# BPC_PWR_Temp_Sensor.net
KiCad netlist of a schematic drawn in Altium Designer
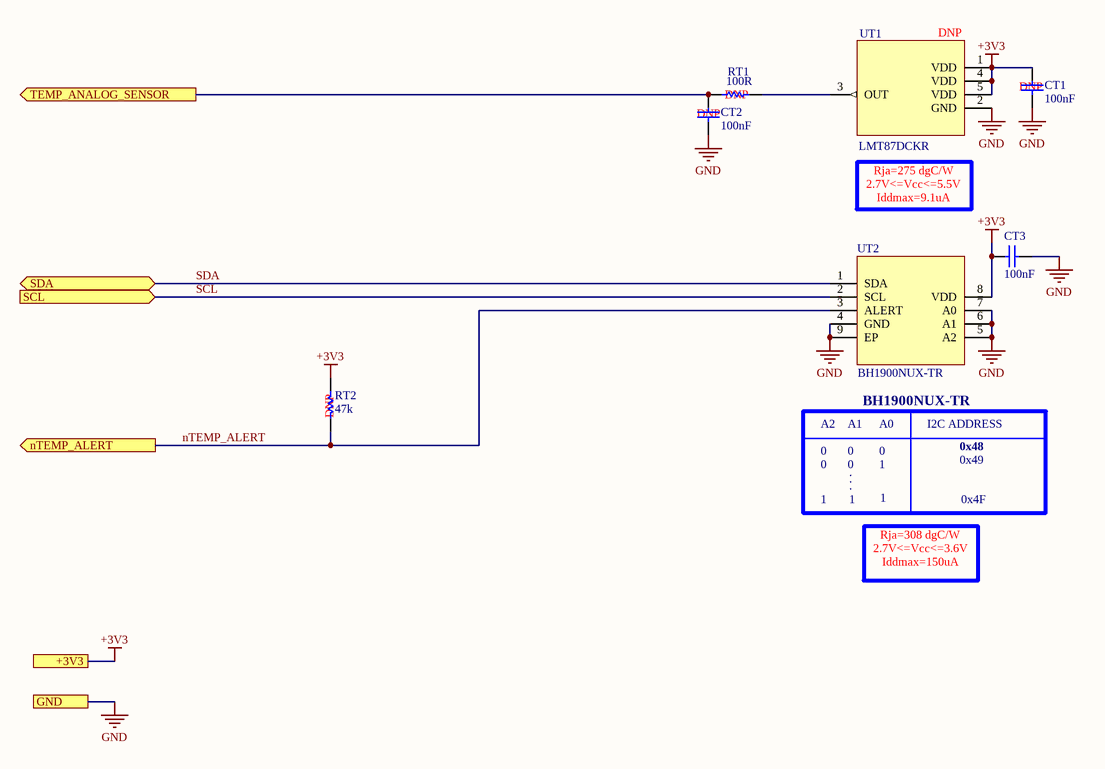
[diagram p0: BPC_PWR_Temp_Sensor.SchDoc]

(export (version "E")
  (design (tool "Eeschema 10.0.6"))
  (components
    (comp (ref "CT1")
      (value "Ceramic Capacitor")
      (footprint "C0603L 0.8 MM MS")
      (description "Ceramic Capacitor 100nF 50V X7R 0603")
      (fields
        (field (name "DISTRIBUTOR PART NUMBER") "187-CL10B104KB8WPNC")
        (field (name "MANUFACTURER") "Samsung Electro-Mechanics")
        (field (name "POPULATED") "DNP")
        (field (name "CAPACITANCE") "100nF")
      )
      (libsource (lib "MS IMP Library") (part "Cap Cer 100nF 50V X7R 0603 Pt02"))
    )
    (comp (ref "CT2")
      (value "Ceramic Capacitor")
      (footprint "C0603L 0.8 MM MS")
      (description "Ceramic Capacitor 100nF 50V X7R 0603")
      (fields
        (field (name "DISTRIBUTOR PART NUMBER") "187-CL10B104KB8WPNC")
        (field (name "MANUFACTURER") "Samsung Electro-Mechanics")
        (field (name "POPULATED") "DNP")
        (field (name "CAPACITANCE") "100nF")
      )
      (libsource (lib "MS IMP Library") (part "Cap Cer 100nF 50V X7R 0603 Pt02"))
    )
    (comp (ref "CT3")
      (value "Ceramic Capacitor")
      (footprint "C0603L 0.8 MM MS")
      (description "Ceramic Capacitor 100nF 50V X7R 0603")
      (fields
        (field (name "DISTRIBUTOR PART NUMBER") "187-CL10B104KB8WPNC")
        (field (name "MANUFACTURER") "Samsung Electro-Mechanics")
        (field (name "CAPACITANCE") "100nF")
      )
      (libsource (lib "MS IMP Library") (part "Cap Cer 100nF 50V X7R 0603 Pt02"))
    )
    (comp (ref "RT1")
      (value "Resistor")
      (footprint "R0603L 0.45MM MS")
      (description "Resistor 100R 1% 100mW 0603")
      (fields
        (field (name "DISTRIBUTOR PART NUMBER") "RMCF0603FT100RCT-ND")
        (field (name "MANUFACTURER") "Stackpole Electronics Inc")
        (field (name "POPULATED") "DNP")
        (field (name "RESISTANCE") "100R")
      )
      (libsource (lib "MS IMP Library") (part "Res 100R 1% 100mW 0603 MS Pt02"))
    )
    (comp (ref "RT2")
      (value "Resistor")
      (footprint "R0603L 0.45MM MS")
      (description "Resistor 47k 1% 100mW 0603")
      (fields
        (field (name "DISTRIBUTOR PART NUMBER") "YAG3355CT-ND")
        (field (name "MANUFACTURER") "Yageo")
        (field (name "POPULATED") "DNP")
        (field (name "RESISTANCE") "47k")
      )
      (libsource (lib "MS IMP Library") (part "Res 47k 1% 100mW 0603 MS"))
    )
    (comp (ref "UT1")
      (value "LMT87DCKR")
      (footprint "DCK5 MS")
      (description "SENSOR ANALOG -50C-150C SC70-5")
      (fields
        (field (name "DISTRIBUTOR PART NUMBER") "595-LMT87DCKR")
        (field (name "MANUFACTURER") "Texas Instruments")
        (field (name "POPULATED") "DNP")
      )
      (libsource (lib "MS IMP Library") (part "IC LMT87DCKR MS"))
    )
    (comp (ref "UT2")
      (value "BH1900NUX-TR")
      (footprint "SON50P300X200X60-9N-D ms")
      (description "SENSOR DGTL -20C-85C 8VSON")
      (fields
        (field (name "DISTRIBUTOR PART NUMBER") "755-BH1900NUX-TR296-29100-1-ND")
        (field (name "MANUFACTURER") "ROHM Semiconductor")
      )
      (libsource (lib "MS IMP Library") (part "IC BH1900NUX-TR MS"))
    )
  )
  (nets
    (net (code "1") (name "+3V3") (class "Default")
      (node (ref "CT1") (pin "2") (pinfunction "2_2") (pintype "passive"))
      (node (ref "CT3") (pin "2") (pinfunction "2_2") (pintype "passive"))
      (node (ref "RT2") (pin "2") (pinfunction "2_2") (pintype "passive"))
      (node (ref "UT1") (pin "1") (pinfunction "VDD_1") (pintype "power_in"))
      (node (ref "UT1") (pin "4") (pinfunction "VDD_4") (pintype "power_in"))
      (node (ref "UT1") (pin "5") (pinfunction "VDD_5") (pintype "power_in"))
      (node (ref "UT2") (pin "8") (pinfunction "VDD_8") (pintype "passive"))
    )
    (net (code "2") (name "/SCL") (class "Default")
      (node (ref "UT2") (pin "2") (pinfunction "SCL_2") (pintype "passive"))
    )
    (net (code "3") (name "/SDA") (class "Default")
      (node (ref "UT2") (pin "1") (pinfunction "SDA_1") (pintype "passive"))
    )
    (net (code "4") (name "/TEMP_ANALOG_SENSOR") (class "Default")
      (node (ref "CT2") (pin "2") (pinfunction "2_2") (pintype "passive"))
      (node (ref "RT1") (pin "1") (pinfunction "1_1") (pintype "passive"))
    )
    (net (code "5") (name "/nTEMP_ALERT") (class "Default")
      (node (ref "RT2") (pin "1") (pinfunction "1_1") (pintype "passive"))
      (node (ref "UT2") (pin "3") (pinfunction "ALERT_3") (pintype "passive"))
    )
    (net (code "6") (name "GND") (class "Default")
      (node (ref "CT1") (pin "1") (pinfunction "1_1") (pintype "passive"))
      (node (ref "CT2") (pin "1") (pinfunction "1_1") (pintype "passive"))
      (node (ref "CT3") (pin "1") (pinfunction "1_1") (pintype "passive"))
      (node (ref "UT1") (pin "2") (pinfunction "GND_2") (pintype "power_in"))
      (node (ref "UT2") (pin "4") (pinfunction "GND_4") (pintype "passive"))
      (node (ref "UT2") (pin "5") (pinfunction "A2_5") (pintype "passive"))
      (node (ref "UT2") (pin "6") (pinfunction "A1_6") (pintype "passive"))
      (node (ref "UT2") (pin "7") (pinfunction "A0_7") (pintype "passive"))
      (node (ref "UT2") (pin "9") (pinfunction "EP_9") (pintype "passive"))
    )
    (net (code "7") (name "Net-(UT1-OUT)") (class "Default")
      (node (ref "RT1") (pin "2") (pinfunction "2_2") (pintype "passive"))
      (node (ref "UT1") (pin "3") (pinfunction "OUT_3") (pintype "output"))
    )
  )
)
